# Camera_IR.net
KiCad netlist of a schematic drawn in EasyEDA
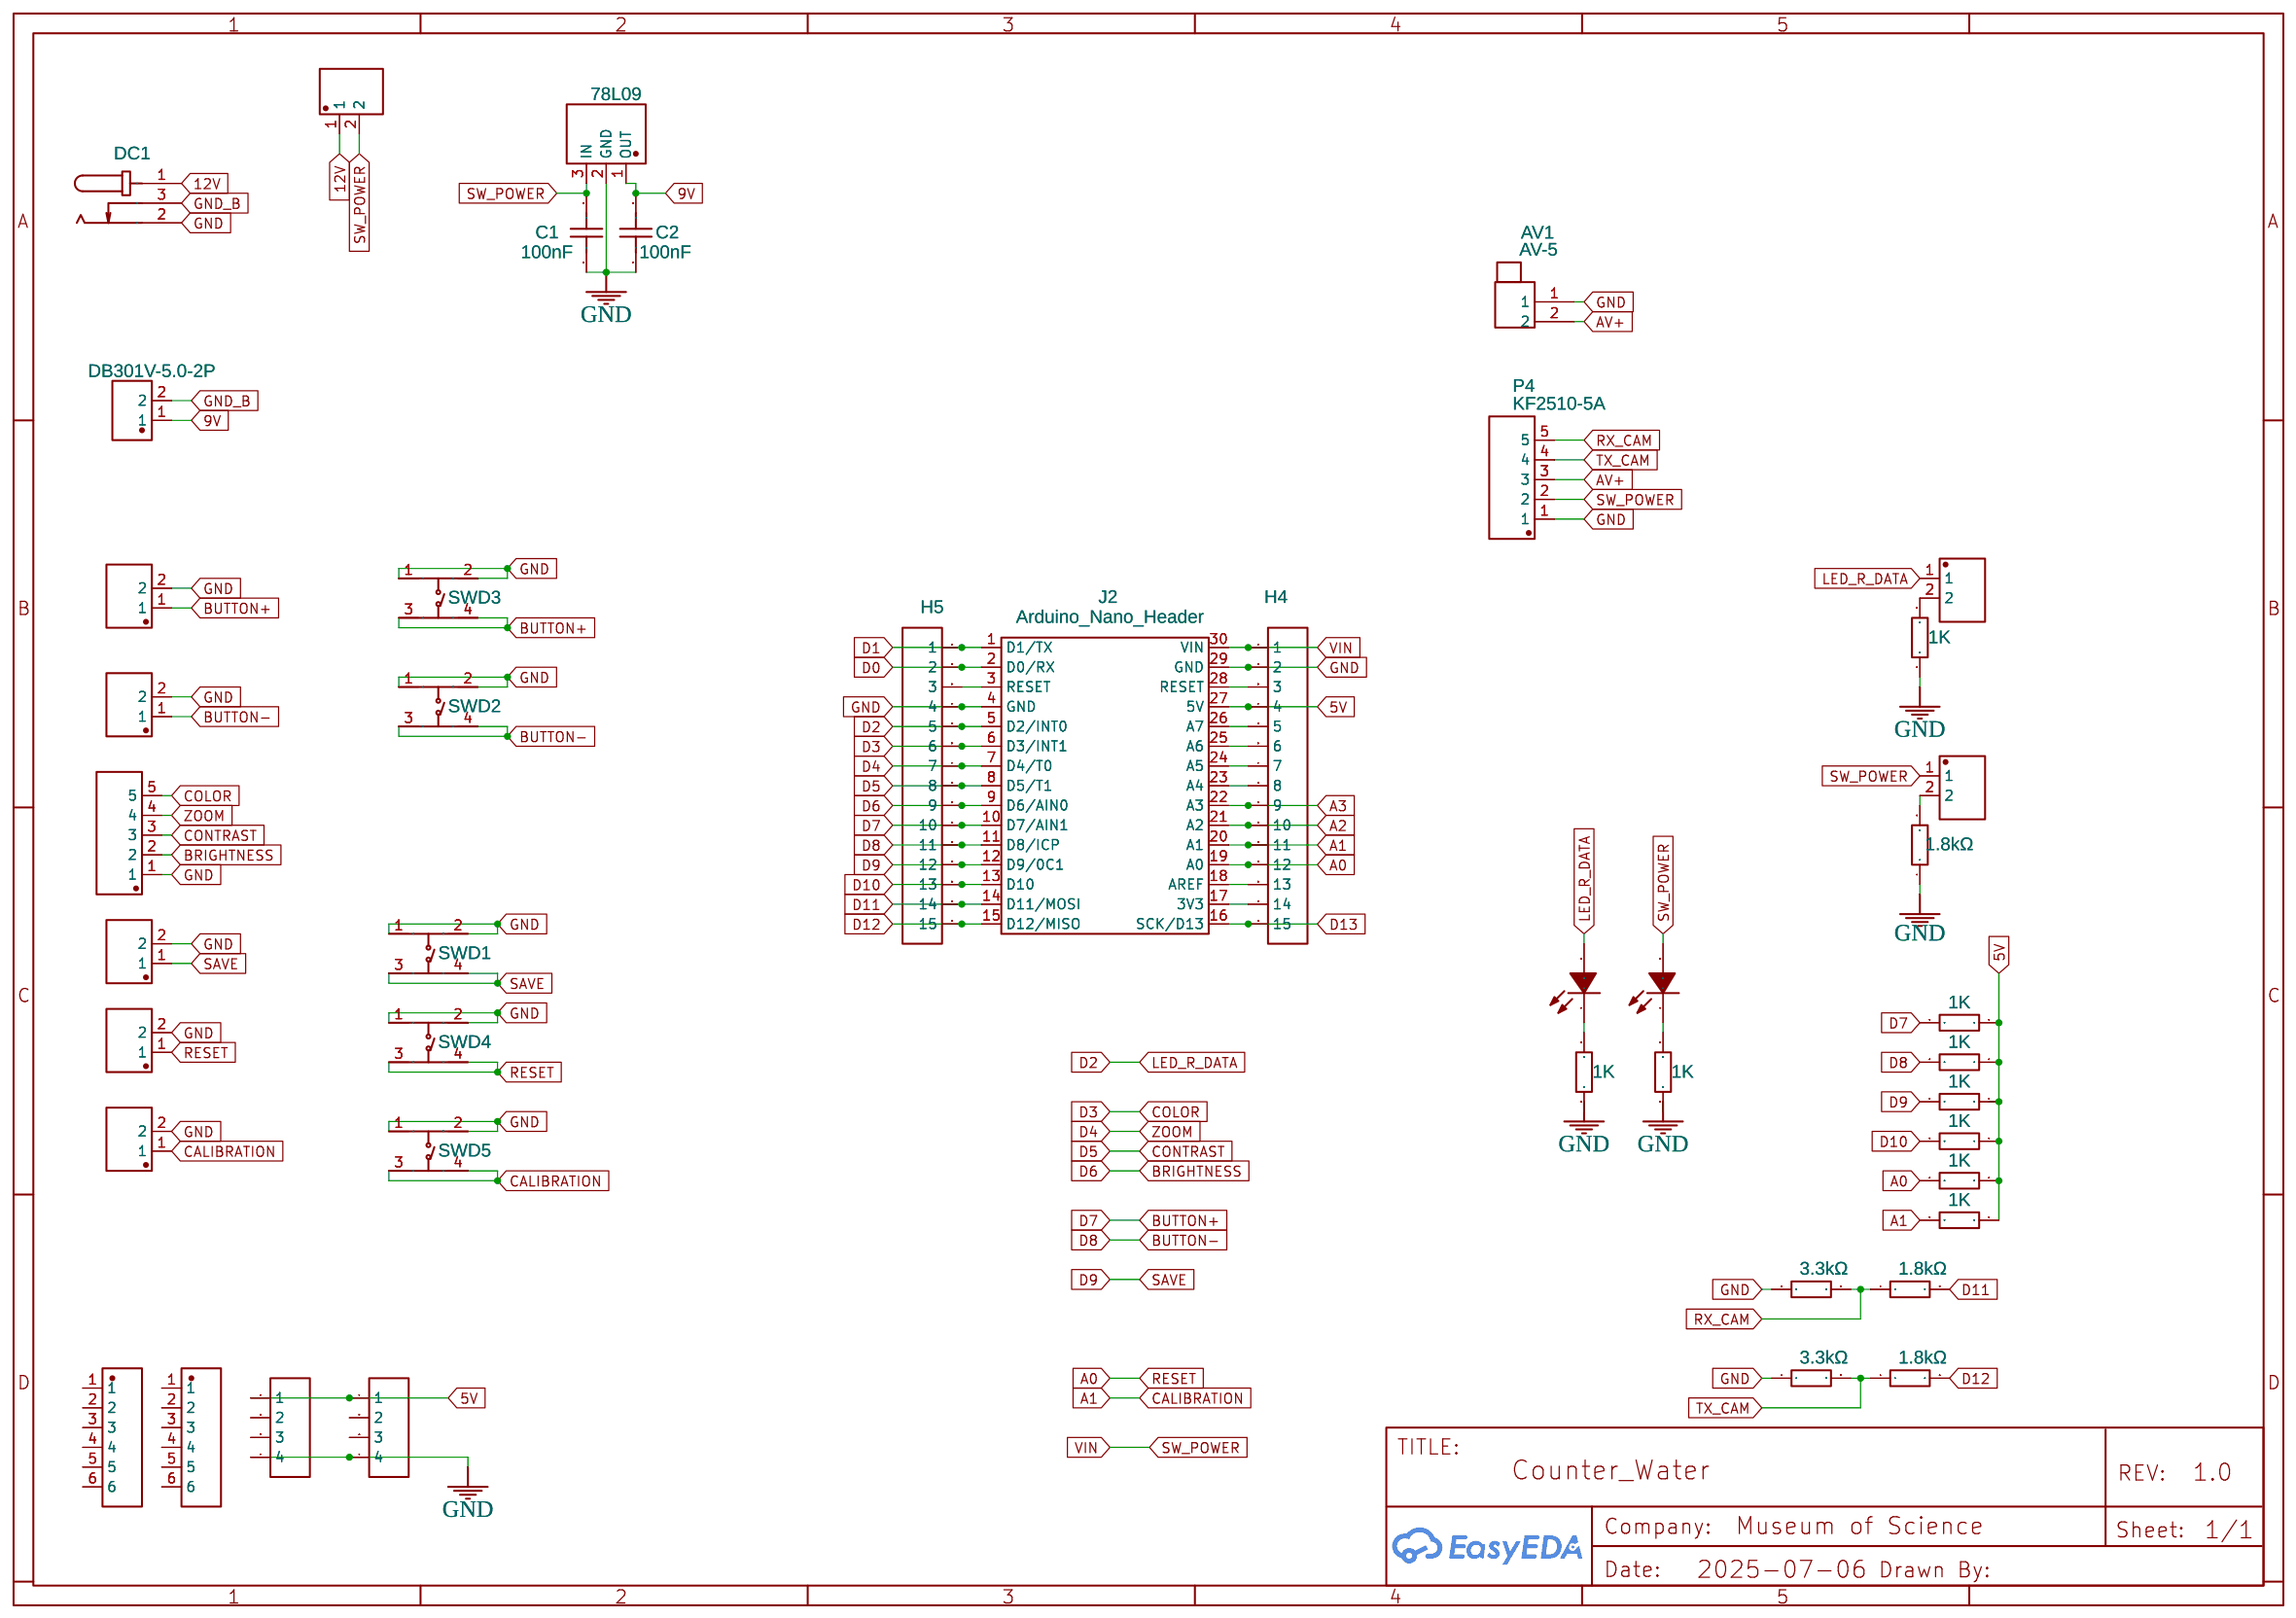
[diagram p0: schematic sheet]

(export (version "E")
  (design (tool "Eeschema 10.0.6"))
  (components
    (comp (ref "A0")
      (value "RESET")
      (fields (field (name "Manufacturer Part") "KF2510-2A") (field (name "Manufacturer") "BOOMELE"))
      (libsource (lib "") (part "KF2510-2A"))
    )
    (comp (ref "A1")
      (value "FFC")
      (fields (field (name "Manufacturer Part") "KF2510-2A") (field (name "Manufacturer") "BOOMELE"))
      (libsource (lib "") (part "KF2510-2A"))
    )
    (comp (ref "AV1")
      (value "AV-5")
      (fields (field (name "Manufacturer") "BOOMELE(博穆精密)"))
      (libsource (lib "") (part "AV-5"))
    )
    (comp (ref "C1")
      (value "100nF")
      (fields
        (field (name "Manufacturer Part") "CC0603KRX7R9BB104")
        (field (name "Manufacturer") "YAGEO(国巨)")
      )
      (libsource (lib "") (part "CC0603KRX7R9BB104"))
    )
    (comp (ref "C2")
      (value "100nF")
      (fields
        (field (name "Manufacturer Part") "CC0603KRX7R9BB104")
        (field (name "Manufacturer") "YAGEO(国巨)")
      )
      (libsource (lib "") (part "CC0603KRX7R9BB104"))
    )
    (comp (ref "D2")
      (value "LED")
      (fields (field (name "Manufacturer Part") "KF2510-2A") (field (name "Manufacturer") "BOOMELE"))
      (libsource (lib "") (part "KF2510-2A_4"))
    )
    (comp (ref "D7")
      (value "B+")
      (fields (field (name "Manufacturer Part") "KF2510-2A") (field (name "Manufacturer") "BOOMELE"))
      (libsource (lib "") (part "KF2510-2A_2"))
    )
    (comp (ref "D8")
      (value "B-")
      (fields (field (name "Manufacturer Part") "KF2510-2A") (field (name "Manufacturer") "BOOMELE"))
      (libsource (lib "") (part "KF2510-2A_2"))
    )
    (comp (ref "D9")
      (value "SAVE")
      (fields (field (name "Manufacturer Part") "KF2510-2A") (field (name "Manufacturer") "BOOMELE"))
      (libsource (lib "") (part "KF2510-2A_2"))
    )
    (comp (ref "DC1")
      (value "DC")
      (fields (field (name "Manufacturer Part") "DC005-2.0MM") (field (name "Manufacturer") "SOFNG"))
      (libsource (lib "") (part "DC005-2.0MM"))
    )
    (comp (ref "ERL1")
      (value "1K")
      (fields (field (name "Manufacturer Part") "0603WAF1001T5E") (field (name "Manufacturer") "UniOhm"))
      (libsource (lib "") (part "0603WAF1001T5E_1"))
    )
    (comp (ref "ERL2")
      (value "1K")
      (fields (field (name "Manufacturer Part") "0603WAF1001T5E") (field (name "Manufacturer") "UniOhm"))
      (libsource (lib "") (part "0603WAF1001T5E"))
    )
    (comp (ref "ERL3")
      (value "1K")
      (fields (field (name "Manufacturer Part") "0603WAF1001T5E") (field (name "Manufacturer") "UniOhm"))
      (libsource (lib "") (part "0603WAF1001T5E"))
    )
    (comp (ref "ERL4")
      (value "1K")
      (fields (field (name "Manufacturer Part") "0603WAF1001T5E") (field (name "Manufacturer") "UniOhm"))
      (libsource (lib "") (part "0603WAF1001T5E_1"))
    )
    (comp (ref "ERL5")
      (value "1K")
      (fields (field (name "Manufacturer Part") "0603WAF1001T5E") (field (name "Manufacturer") "UniOhm"))
      (libsource (lib "") (part "0603WAF1001T5E_1"))
    )
    (comp (ref "ERL6")
      (value "1K")
      (fields (field (name "Manufacturer Part") "0603WAF1001T5E") (field (name "Manufacturer") "UniOhm"))
      (libsource (lib "") (part "0603WAF1001T5E"))
    )
    (comp (ref "ERL9")
      (value "1K")
      (fields (field (name "Manufacturer Part") "0603WAF1001T5E") (field (name "Manufacturer") "UniOhm"))
      (libsource (lib "") (part "0603WAF1001T5E"))
    )
    (comp (ref "ERL11")
      (value "1K")
      (fields (field (name "Manufacturer Part") "0603WAF1001T5E") (field (name "Manufacturer") "UniOhm"))
      (libsource (lib "") (part "0603WAF1001T5E"))
    )
    (comp (ref "ERL12")
      (value "1K")
      (fields (field (name "Manufacturer Part") "0603WAF1001T5E") (field (name "Manufacturer") "UniOhm"))
      (libsource (lib "") (part "0603WAF1001T5E"))
    )
    (comp (ref "H4") (value "HDR-F-2.54_1x15") (libsource (lib "") (part "HDR-F-2.54_1x15")))
    (comp (ref "H5") (value "HDR-F-2.54_1x15") (libsource (lib "") (part "HDR-F-2.54_1x15_1")))
    (comp (ref "J2") (value "Arduino_Nano_Header") (libsource (lib "") (part "Arduino_Nano_Header")))
    (comp (ref "J6") (value "HDR-M-2.54_1x4") (libsource (lib "") (part "HDR-M-2.54_1x4")))
    (comp (ref "J7") (value "HDR-M-2.54_1x4") (libsource (lib "") (part "HDR-M-2.54_1x4")))
    (comp (ref "LED4")
      (value "KT-0603R")
      (fields (field (name "Manufacturer") "KENTO"))
      (libsource (lib "") (part "KT-0603R"))
    )
    (comp (ref "LED5")
      (value "KT-0603R")
      (fields (field (name "Manufacturer") "KENTO"))
      (libsource (lib "") (part "KT-0603R"))
    )
    (comp (ref "LED_P")
      (value "LED_POWER")
      (fields (field (name "Manufacturer Part") "KF2510-2A") (field (name "Manufacturer") "BOOMELE"))
      (libsource (lib "") (part "KF2510-2A_3"))
    )
    (comp (ref "P1")
      (value "KF2510-5A")
      (fields (field (name "Manufacturer Part") "2510-5A") (field (name "Manufacturer") "BOOMELE(博穆精密)"))
      (libsource (lib "") (part "KF2510-5A"))
    )
    (comp (ref "P2")
      (value "H6")
      (fields (field (name "Manufacturer Part") "2.54-1*6P母") (field (name "Manufacturer") "BOOMELE(博穆精密)"))
      (libsource (lib "") (part "Header-Female-2.54_1x6"))
    )
    (comp (ref "P3")
      (value "H6")
      (fields (field (name "Manufacturer Part") "2.54-1*6P母") (field (name "Manufacturer") "BOOMELE(博穆精密)"))
      (libsource (lib "") (part "Header-Female-2.54_1x6"))
    )
    (comp (ref "P4")
      (value "KF2510-5A")
      (fields (field (name "Manufacturer Part") "2510-5A") (field (name "Manufacturer") "BOOMELE(博穆精密)"))
      (libsource (lib "") (part "KF2510-5A"))
    )
    (comp (ref "R1")
      (value "1.8kΩ")
      (fields
        (field (name "Manufacturer Part") "0603WAF1801T5E")
        (field (name "Manufacturer") "UNI-ROYAL(厚声)")
      )
      (libsource (lib "") (part "0603WAF1801T5E_1"))
    )
    (comp (ref "R2")
      (value "1.8kΩ")
      (fields
        (field (name "Manufacturer Part") "0603WAF1801T5E")
        (field (name "Manufacturer") "UNI-ROYAL(厚声)")
      )
      (libsource (lib "") (part "0603WAF1801T5E_1"))
    )
    (comp (ref "R3")
      (value "3.3kΩ")
      (fields
        (field (name "Manufacturer Part") "0402WGF3301TCE")
        (field (name "Manufacturer") "UNI-ROYAL(厚声)")
      )
      (libsource (lib "") (part "0402WGF3301TCE"))
    )
    (comp (ref "R4")
      (value "3.3kΩ")
      (fields
        (field (name "Manufacturer Part") "0402WGF3301TCE")
        (field (name "Manufacturer") "UNI-ROYAL(厚声)")
      )
      (libsource (lib "") (part "0402WGF3301TCE"))
    )
    (comp (ref "R5")
      (value "1.8kΩ")
      (fields
        (field (name "Manufacturer Part") "0603WAF1801T5E")
        (field (name "Manufacturer") "UNI-ROYAL(厚声)")
      )
      (libsource (lib "") (part "0603WAF1801T5E"))
    )
    (comp (ref "SWD1")
      (value "TC-6610-7-160G")
      (fields (field (name "Manufacturer") "HCTL(华灿天禄)"))
      (libsource (lib "") (part "TC-6610-7-160G"))
    )
    (comp (ref "SWD2")
      (value "TC-6610-7-160G")
      (fields (field (name "Manufacturer") "HCTL(华灿天禄)"))
      (libsource (lib "") (part "TC-6610-7-160G"))
    )
    (comp (ref "SWD3")
      (value "TC-6610-7-160G")
      (fields (field (name "Manufacturer") "HCTL(华灿天禄)"))
      (libsource (lib "") (part "TC-6610-7-160G"))
    )
    (comp (ref "SWD4")
      (value "TC-6610-7-160G")
      (fields (field (name "Manufacturer") "HCTL(华灿天禄)"))
      (libsource (lib "") (part "TC-6610-7-160G"))
    )
    (comp (ref "SWD5")
      (value "TC-6610-7-160G")
      (fields (field (name "Manufacturer") "HCTL(华灿天禄)"))
      (libsource (lib "") (part "TC-6610-7-160G"))
    )
    (comp (ref "SW_P")
      (value "SW_P")
      (fields (field (name "Manufacturer Part") "KF2510-2A") (field (name "Manufacturer") "BOOMELE"))
      (libsource (lib "") (part "KF2510-2A_1"))
    )
    (comp (ref "U1")
      (value "78L09")
      (fields (field (name "Manufacturer") "CBI(创基)"))
      (libsource (lib "") (part "78L09U 78L09"))
    )
    (comp (ref "U3")
      (value "DB301V-5.0-2P")
      (fields
        (field (name "Manufacturer Part") "DB301V-5.0-2P-BU-S")
        (field (name "Manufacturer") "DORABO(地博电气)")
      )
      (libsource (lib "") (part "DB301V-5.0-2P"))
    )
  )
  (nets
    (net (code "1") (name "5V") (class "Default")
      (node (ref "ERL11") (pin "1") (pinfunction "1_1") (pintype "input"))
      (node (ref "ERL12") (pin "1") (pinfunction "1_1") (pintype "input"))
      (node (ref "ERL2") (pin "1") (pinfunction "1_1") (pintype "input"))
      (node (ref "ERL3") (pin "1") (pinfunction "1_1") (pintype "input"))
      (node (ref "ERL6") (pin "1") (pinfunction "1_1") (pintype "input"))
      (node (ref "ERL9") (pin "1") (pinfunction "1_1") (pintype "input"))
      (node (ref "H4") (pin "4") (pinfunction "4_4") (pintype "unspecified"))
      (node (ref "J2") (pin "27") (pinfunction "5V_27") (pintype "unspecified"))
      (node (ref "J6") (pin "1") (pinfunction "1_1") (pintype "unspecified"))
      (node (ref "J7") (pin "1") (pinfunction "1_1") (pintype "unspecified"))
    )
    (net (code "2") (name "9V") (class "Default")
      (node (ref "C2") (pin "2") (pinfunction "2_2") (pintype "unspecified"))
      (node (ref "U1") (pin "1") (pinfunction "OUT_1") (pintype "unspecified"))
      (node (ref "U3") (pin "1") (pinfunction "1_1") (pintype "unspecified"))
    )
    (net (code "3") (name "12V") (class "Default")
      (node (ref "DC1") (pin "1") (pinfunction "1_1") (pintype "unspecified"))
      (node (ref "SW_P") (pin "1") (pinfunction "1_1") (pintype "unspecified"))
    )
    (net (code "4") (name "A0") (class "Default")
      (node (ref "A0") (pin "1") (pinfunction "1_1") (pintype "unspecified"))
      (node (ref "ERL2") (pin "2") (pinfunction "2_2") (pintype "input"))
      (node (ref "H4") (pin "12") (pinfunction "12_12") (pintype "unspecified"))
      (node (ref "J2") (pin "19") (pinfunction "A0_19") (pintype "unspecified"))
      (node (ref "SWD4") (pin "3") (pinfunction "3_3") (pintype "unspecified"))
      (node (ref "SWD4") (pin "4") (pinfunction "4_4") (pintype "unspecified"))
    )
    (net (code "5") (name "A1") (class "Default")
      (node (ref "A1") (pin "1") (pinfunction "1_1") (pintype "unspecified"))
      (node (ref "ERL3") (pin "2") (pinfunction "2_2") (pintype "input"))
      (node (ref "H4") (pin "11") (pinfunction "11_11") (pintype "unspecified"))
      (node (ref "J2") (pin "20") (pinfunction "A1_20") (pintype "unspecified"))
      (node (ref "SWD5") (pin "3") (pinfunction "3_3") (pintype "unspecified"))
      (node (ref "SWD5") (pin "4") (pinfunction "4_4") (pintype "unspecified"))
    )
    (net (code "6") (name "A2") (class "Default")
      (node (ref "H4") (pin "10") (pinfunction "10_10") (pintype "unspecified"))
      (node (ref "J2") (pin "21") (pinfunction "A2_21") (pintype "unspecified"))
    )
    (net (code "7") (name "A3") (class "Default")
      (node (ref "H4") (pin "9") (pinfunction "9_9") (pintype "unspecified"))
      (node (ref "J2") (pin "22") (pinfunction "A3_22") (pintype "unspecified"))
    )
    (net (code "8") (name "AV+") (class "Default")
      (node (ref "AV1") (pin "2") (pinfunction "2_2") (pintype "unspecified"))
      (node (ref "P4") (pin "3") (pinfunction "3_3") (pintype "unspecified"))
    )
    (net (code "9") (name "BRIGHTNESS") (class "Default")
      (node (ref "H5") (pin "9") (pinfunction "9_9") (pintype "unspecified"))
      (node (ref "J2") (pin "9") (pinfunction "D6/AIN0_9") (pintype "unspecified"))
      (node (ref "P1") (pin "2") (pinfunction "2_2") (pintype "unspecified"))
    )
    (net (code "10") (name "BUTTON+") (class "Default")
      (node (ref "D7") (pin "1") (pinfunction "1_1") (pintype "unspecified"))
      (node (ref "ERL6") (pin "2") (pinfunction "2_2") (pintype "input"))
      (node (ref "H5") (pin "10") (pinfunction "10_10") (pintype "unspecified"))
      (node (ref "J2") (pin "10") (pinfunction "D7/AIN1_10") (pintype "unspecified"))
      (node (ref "SWD3") (pin "3") (pinfunction "3_3") (pintype "unspecified"))
      (node (ref "SWD3") (pin "4") (pinfunction "4_4") (pintype "unspecified"))
    )
    (net (code "11") (name "BUTTON-") (class "Default")
      (node (ref "D8") (pin "1") (pinfunction "1_1") (pintype "unspecified"))
      (node (ref "ERL11") (pin "2") (pinfunction "2_2") (pintype "input"))
      (node (ref "H5") (pin "11") (pinfunction "11_11") (pintype "unspecified"))
      (node (ref "J2") (pin "11") (pinfunction "D8/ICP_11") (pintype "unspecified"))
      (node (ref "SWD2") (pin "3") (pinfunction "3_3") (pintype "unspecified"))
      (node (ref "SWD2") (pin "4") (pinfunction "4_4") (pintype "unspecified"))
    )
    (net (code "12") (name "COLOR") (class "Default")
      (node (ref "H5") (pin "6") (pinfunction "6_6") (pintype "unspecified"))
      (node (ref "J2") (pin "6") (pinfunction "D3/INT1_6") (pintype "unspecified"))
      (node (ref "P1") (pin "5") (pinfunction "5_5") (pintype "unspecified"))
    )
    (net (code "13") (name "CONTRAST") (class "Default")
      (node (ref "H5") (pin "8") (pinfunction "8_8") (pintype "unspecified"))
      (node (ref "J2") (pin "8") (pinfunction "D5/T1_8") (pintype "unspecified"))
      (node (ref "P1") (pin "3") (pinfunction "3_3") (pintype "unspecified"))
    )
    (net (code "14") (name "D0") (class "Default")
      (node (ref "H5") (pin "2") (pinfunction "2_2") (pintype "unspecified"))
      (node (ref "J2") (pin "2") (pinfunction "D0/RX_2") (pintype "unspecified"))
    )
    (net (code "15") (name "D1") (class "Default")
      (node (ref "H5") (pin "1") (pinfunction "1_1") (pintype "unspecified"))
      (node (ref "J2") (pin "1") (pinfunction "D1/TX_1") (pintype "unspecified"))
    )
    (net (code "16") (name "D2") (class "Default")
      (node (ref "D2") (pin "1") (pinfunction "1_1") (pintype "unspecified"))
      (node (ref "H5") (pin "5") (pinfunction "5_5") (pintype "unspecified"))
      (node (ref "J2") (pin "5") (pinfunction "D2/INT0_5") (pintype "unspecified"))
      (node (ref "LED5") (pin "2") (pinfunction "A_2") (pintype "unspecified"))
    )
    (net (code "17") (name "D4") (class "Default")
      (node (ref "H5") (pin "7") (pinfunction "7_7") (pintype "unspecified"))
      (node (ref "J2") (pin "7") (pinfunction "D4/T0_7") (pintype "unspecified"))
      (node (ref "P1") (pin "4") (pinfunction "4_4") (pintype "unspecified"))
    )
    (net (code "18") (name "D9") (class "Default")
      (node (ref "D9") (pin "1") (pinfunction "1_1") (pintype "unspecified"))
      (node (ref "ERL9") (pin "2") (pinfunction "2_2") (pintype "input"))
      (node (ref "H5") (pin "12") (pinfunction "12_12") (pintype "unspecified"))
      (node (ref "J2") (pin "12") (pinfunction "D9/0C1_12") (pintype "unspecified"))
      (node (ref "SWD1") (pin "3") (pinfunction "3_3") (pintype "unspecified"))
      (node (ref "SWD1") (pin "4") (pinfunction "4_4") (pintype "unspecified"))
    )
    (net (code "19") (name "D10") (class "Default")
      (node (ref "ERL12") (pin "2") (pinfunction "2_2") (pintype "input"))
      (node (ref "H5") (pin "13") (pinfunction "13_13") (pintype "unspecified"))
      (node (ref "J2") (pin "13") (pinfunction "D10_13") (pintype "unspecified"))
    )
    (net (code "20") (name "D11") (class "Default")
      (node (ref "H5") (pin "14") (pinfunction "14_14") (pintype "unspecified"))
      (node (ref "J2") (pin "14") (pinfunction "D11/MOSI_14") (pintype "unspecified"))
      (node (ref "R1") (pin "2") (pinfunction "2_2") (pintype "input"))
    )
    (net (code "21") (name "D12") (class "Default")
      (node (ref "H5") (pin "15") (pinfunction "15_15") (pintype "unspecified"))
      (node (ref "J2") (pin "15") (pinfunction "D12/MISO_15") (pintype "unspecified"))
      (node (ref "R2") (pin "2") (pinfunction "2_2") (pintype "input"))
    )
    (net (code "22") (name "D13") (class "Default")
      (node (ref "H4") (pin "15") (pinfunction "15_15") (pintype "unspecified"))
      (node (ref "J2") (pin "16") (pinfunction "SCK/D13_16") (pintype "unspecified"))
    )
    (net (code "23") (name "GND") (class "Default")
      (node (ref "A0") (pin "2") (pinfunction "2_2") (pintype "unspecified"))
      (node (ref "A1") (pin "2") (pinfunction "2_2") (pintype "unspecified"))
      (node (ref "AV1") (pin "1") (pinfunction "1_1") (pintype "unspecified"))
      (node (ref "C1") (pin "1") (pinfunction "1_1") (pintype "unspecified"))
      (node (ref "C2") (pin "1") (pinfunction "1_1") (pintype "unspecified"))
      (node (ref "D7") (pin "2") (pinfunction "2_2") (pintype "unspecified"))
      (node (ref "D8") (pin "2") (pinfunction "2_2") (pintype "unspecified"))
      (node (ref "D9") (pin "2") (pinfunction "2_2") (pintype "unspecified"))
      (node (ref "DC1") (pin "2") (pinfunction "2_2") (pintype "unspecified"))
      (node (ref "ERL1") (pin "1") (pinfunction "1_1") (pintype "input"))
      (node (ref "ERL4") (pin "1") (pinfunction "1_1") (pintype "input"))
      (node (ref "ERL5") (pin "1") (pinfunction "1_1") (pintype "input"))
      (node (ref "H4") (pin "2") (pinfunction "2_2") (pintype "unspecified"))
      (node (ref "H5") (pin "4") (pinfunction "4_4") (pintype "unspecified"))
      (node (ref "J2") (pin "29") (pinfunction "GND_29") (pintype "unspecified"))
      (node (ref "J2") (pin "4") (pinfunction "GND_4") (pintype "unspecified"))
      (node (ref "J6") (pin "4") (pinfunction "4_4") (pintype "unspecified"))
      (node (ref "J7") (pin "4") (pinfunction "4_4") (pintype "unspecified"))
      (node (ref "P1") (pin "1") (pinfunction "1_1") (pintype "unspecified"))
      (node (ref "P4") (pin "1") (pinfunction "1_1") (pintype "unspecified"))
      (node (ref "R3") (pin "1") (pinfunction "1_1") (pintype "input"))
      (node (ref "R4") (pin "1") (pinfunction "1_1") (pintype "input"))
      (node (ref "R5") (pin "1") (pinfunction "1_1") (pintype "input"))
      (node (ref "SWD1") (pin "1") (pinfunction "1_1") (pintype "unspecified"))
      (node (ref "SWD1") (pin "2") (pinfunction "2_2") (pintype "unspecified"))
      (node (ref "SWD2") (pin "1") (pinfunction "1_1") (pintype "unspecified"))
      (node (ref "SWD2") (pin "2") (pinfunction "2_2") (pintype "unspecified"))
      (node (ref "SWD3") (pin "1") (pinfunction "1_1") (pintype "unspecified"))
      (node (ref "SWD3") (pin "2") (pinfunction "2_2") (pintype "unspecified"))
      (node (ref "SWD4") (pin "1") (pinfunction "1_1") (pintype "unspecified"))
      (node (ref "SWD4") (pin "2") (pinfunction "2_2") (pintype "unspecified"))
      (node (ref "SWD5") (pin "1") (pinfunction "1_1") (pintype "unspecified"))
      (node (ref "SWD5") (pin "2") (pinfunction "2_2") (pintype "unspecified"))
      (node (ref "U1") (pin "2") (pinfunction "GND_2") (pintype "unspecified"))
    )
    (net (code "24") (name "GND_B") (class "Default")
      (node (ref "DC1") (pin "3") (pinfunction "3_3") (pintype "unspecified"))
      (node (ref "U3") (pin "2") (pinfunction "2_2") (pintype "unspecified"))
    )
    (net (code "25") (name "Net-(D2-Pad2)") (class "Default")
      (node (ref "D2") (pin "2") (pinfunction "2_2") (pintype "unspecified"))
      (node (ref "ERL5") (pin "2") (pinfunction "2_2") (pintype "input"))
    )
    (net (code "26") (name "Net-(H4-Pad3)") (class "Default")
      (node (ref "H4") (pin "3") (pinfunction "3_3") (pintype "unspecified"))
      (node (ref "J2") (pin "28") (pinfunction "RESET_28") (pintype "unspecified"))
    )
    (net (code "27") (name "Net-(H5-Pad3)") (class "Default")
      (node (ref "H5") (pin "3") (pinfunction "3_3") (pintype "unspecified"))
      (node (ref "J2") (pin "3") (pinfunction "RESET_3") (pintype "unspecified"))
    )
    (net (code "28") (name "Net-(J2-3V3)") (class "Default")
      (node (ref "H4") (pin "14") (pinfunction "14_14") (pintype "unspecified"))
      (node (ref "J2") (pin "17") (pinfunction "3V3_17") (pintype "unspecified"))
    )
    (net (code "29") (name "Net-(J2-A4)") (class "Default")
      (node (ref "H4") (pin "8") (pinfunction "8_8") (pintype "unspecified"))
      (node (ref "J2") (pin "23") (pinfunction "A4_23") (pintype "unspecified"))
    )
    (net (code "30") (name "Net-(J2-A5)") (class "Default")
      (node (ref "H4") (pin "7") (pinfunction "7_7") (pintype "unspecified"))
      (node (ref "J2") (pin "24") (pinfunction "A5_24") (pintype "unspecified"))
    )
    (net (code "31") (name "Net-(J2-A6)") (class "Default")
      (node (ref "H4") (pin "6") (pinfunction "6_6") (pintype "unspecified"))
      (node (ref "J2") (pin "25") (pinfunction "A6_25") (pintype "unspecified"))
    )
    (net (code "32") (name "Net-(J2-A7)") (class "Default")
      (node (ref "H4") (pin "5") (pinfunction "5_5") (pintype "unspecified"))
      (node (ref "J2") (pin "26") (pinfunction "A7_26") (pintype "unspecified"))
    )
    (net (code "33") (name "Net-(J2-AREF)") (class "Default")
      (node (ref "H4") (pin "13") (pinfunction "13_13") (pintype "unspecified"))
      (node (ref "J2") (pin "18") (pinfunction "AREF_18") (pintype "unspecified"))
    )
    (net (code "34") (name "Net-(LED4-K)") (class "Default")
      (node (ref "ERL4") (pin "2") (pinfunction "2_2") (pintype "input"))
      (node (ref "LED4") (pin "1") (pinfunction "K_1") (pintype "unspecified"))
    )
    (net (code "35") (name "Net-(LED5-K)") (class "Default")
      (node (ref "ERL1") (pin "2") (pinfunction "2_2") (pintype "input"))
      (node (ref "LED5") (pin "1") (pinfunction "K_1") (pintype "unspecified"))
    )
    (net (code "36") (name "Net-(LED_P-Pad2)") (class "Default")
      (node (ref "LED_P") (pin "2") (pinfunction "2_2") (pintype "unspecified"))
      (node (ref "R5") (pin "2") (pinfunction "2_2") (pintype "input"))
    )
    (net (code "37") (name "RX_CAM") (class "Default")
      (node (ref "P4") (pin "5") (pinfunction "5_5") (pintype "unspecified"))
      (node (ref "R1") (pin "1") (pinfunction "1_1") (pintype "input"))
      (node (ref "R3") (pin "2") (pinfunction "2_2") (pintype "input"))
    )
    (net (code "38") (name "SW_POWER") (class "Default")
      (node (ref "C1") (pin "2") (pinfunction "2_2") (pintype "unspecified"))
      (node (ref "H4") (pin "1") (pinfunction "1_1") (pintype "unspecified"))
      (node (ref "J2") (pin "30") (pinfunction "VIN_30") (pintype "unspecified"))
      (node (ref "LED4") (pin "2") (pinfunction "A_2") (pintype "unspecified"))
      (node (ref "LED_P") (pin "1") (pinfunction "1_1") (pintype "unspecified"))
      (node (ref "P4") (pin "2") (pinfunction "2_2") (pintype "unspecified"))
      (node (ref "SW_P") (pin "2") (pinfunction "2_2") (pintype "unspecified"))
      (node (ref "U1") (pin "3") (pinfunction "IN_3") (pintype "unspecified"))
    )
    (net (code "39") (name "TX_CAM") (class "Default")
      (node (ref "P4") (pin "4") (pinfunction "4_4") (pintype "unspecified"))
      (node (ref "R2") (pin "1") (pinfunction "1_1") (pintype "input"))
      (node (ref "R4") (pin "2") (pinfunction "2_2") (pintype "input"))
    )
    (net (code "40") (name "unconnected-(J6-Pad2)") (class "Default")
      (node (ref "J6") (pin "2") (pinfunction "2_2") (pintype "unspecified"))
    )
    (net (code "41") (name "unconnected-(J6-Pad3)") (class "Default")
      (node (ref "J6") (pin "3") (pinfunction "3_3") (pintype "unspecified"))
    )
    (net (code "42") (name "unconnected-(J7-Pad2)") (class "Default")
      (node (ref "J7") (pin "2") (pinfunction "2_2") (pintype "unspecified"))
    )
    (net (code "43") (name "unconnected-(J7-Pad3)") (class "Default")
      (node (ref "J7") (pin "3") (pinfunction "3_3") (pintype "unspecified"))
    )
    (net (code "44") (name "unconnected-(P2-Pad1)") (class "Default")
      (node (ref "P2") (pin "1") (pinfunction "1_1") (pintype "unspecified"))
    )
    (net (code "45") (name "unconnected-(P2-Pad2)") (class "Default")
      (node (ref "P2") (pin "2") (pinfunction "2_2") (pintype "unspecified"))
    )
    (net (code "46") (name "unconnected-(P2-Pad3)") (class "Default")
      (node (ref "P2") (pin "3") (pinfunction "3_3") (pintype "unspecified"))
    )
    (net (code "47") (name "unconnected-(P2-Pad4)") (class "Default")
      (node (ref "P2") (pin "4") (pinfunction "4_4") (pintype "unspecified"))
    )
    (net (code "48") (name "unconnected-(P2-Pad5)") (class "Default")
      (node (ref "P2") (pin "5") (pinfunction "5_5") (pintype "unspecified"))
    )
    (net (code "49") (name "unconnected-(P2-Pad6)") (class "Default")
      (node (ref "P2") (pin "6") (pinfunction "6_6") (pintype "unspecified"))
    )
    (net (code "50") (name "unconnected-(P3-Pad1)") (class "Default")
      (node (ref "P3") (pin "1") (pinfunction "1_1") (pintype "unspecified"))
    )
    (net (code "51") (name "unconnected-(P3-Pad2)") (class "Default")
      (node (ref "P3") (pin "2") (pinfunction "2_2") (pintype "unspecified"))
    )
    (net (code "52") (name "unconnected-(P3-Pad3)") (class "Default")
      (node (ref "P3") (pin "3") (pinfunction "3_3") (pintype "unspecified"))
    )
    (net (code "53") (name "unconnected-(P3-Pad4)") (class "Default")
      (node (ref "P3") (pin "4") (pinfunction "4_4") (pintype "unspecified"))
    )
    (net (code "54") (name "unconnected-(P3-Pad5)") (class "Default")
      (node (ref "P3") (pin "5") (pinfunction "5_5") (pintype "unspecified"))
    )
    (net (code "55") (name "unconnected-(P3-Pad6)") (class "Default")
      (node (ref "P3") (pin "6") (pinfunction "6_6") (pintype "unspecified"))
    )
  )
)
